# Nestling_2_1_EXB_OLED.net
KiCad netlist of a schematic drawn in Altium Designer
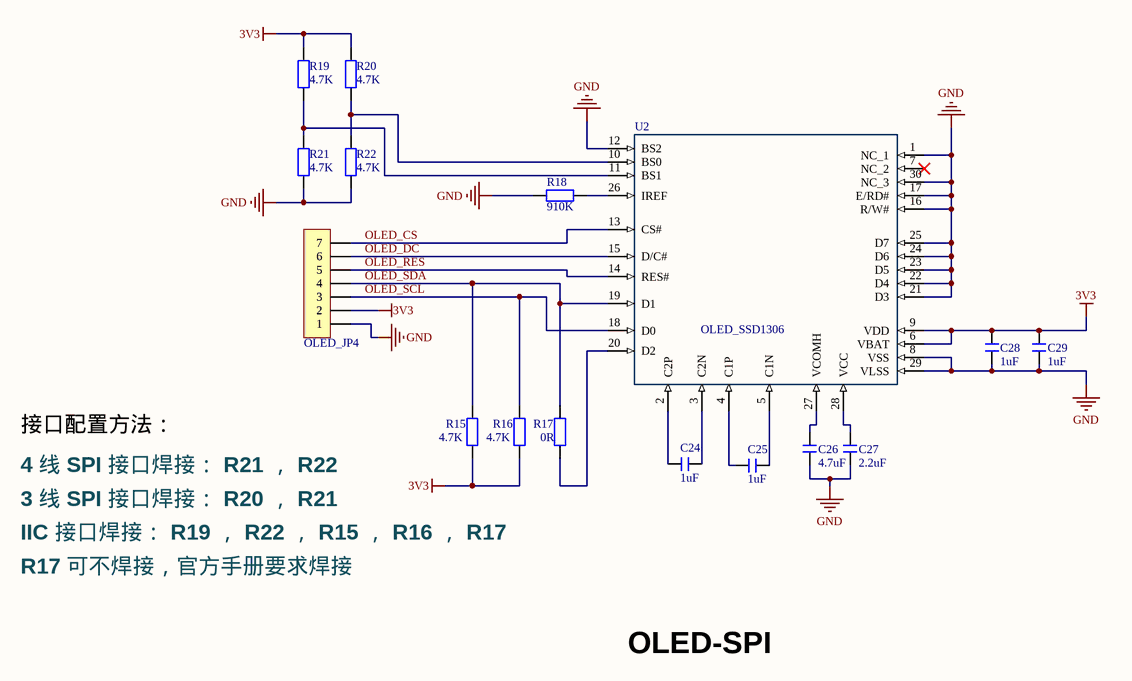
[diagram p0: Nestling_2.1_EXB_OLED.SchDoc]

(export (version "E")
  (design (tool "Eeschema 10.0.6"))
  (components
    (comp (ref "C24")
      (value "1uF")
      (footprint "C 0603_M")
      (description "无极性贴片电容")
      (fields (field (name "版权归属") "源创客"))
      (libsource (lib "altium-import") (part "root_0_C_"))
    )
    (comp (ref "C25")
      (value "1uF")
      (footprint "C 0603_M")
      (description "无极性贴片电容")
      (fields (field (name "版权归属") "源创客"))
      (libsource (lib "altium-import") (part "root_0_C_"))
    )
    (comp (ref "C26")
      (value "4.7uF")
      (footprint "C 0603_M")
      (description "无极性贴片电容")
      (fields (field (name "版权归属") "源创客"))
      (libsource (lib "altium-import") (part "root_3_C_"))
    )
    (comp (ref "C27")
      (value "2.2uF")
      (footprint "C 0603_M")
      (description "无极性贴片电容")
      (fields (field (name "版权归属") "源创客"))
      (libsource (lib "altium-import") (part "root_3_C_"))
    )
    (comp (ref "C28")
      (value "1uF")
      (footprint "C 0603_M")
      (description "无极性贴片电容")
      (fields (field (name "版权归属") "源创客"))
      (libsource (lib "altium-import") (part "root_3_C_"))
    )
    (comp (ref "C29")
      (value "1uF")
      (footprint "C 0603_M")
      (description "无极性贴片电容")
      (fields (field (name "版权归属") "源创客"))
      (libsource (lib "altium-import") (part "root_3_C_"))
    )
    (comp (ref "OLED_JP4")
      (value "HDR-1X7")
      (footprint "HDR2.54-M-LI-7P")
      (description "7P接插件")
      (fields (field (name "版权归属") "源创客"))
      (libsource (lib "altium-import") (part "root_2_Header 7_"))
    )
    (comp (ref "R15")
      (value "4.7K")
      (footprint "R 0603_M")
      (description "Resistor")
      (libsource (lib "General") (part "RES"))
    )
    (comp (ref "R16")
      (value "4.7K")
      (footprint "R 0603_M")
      (description "Resistor")
      (libsource (lib "General") (part "RES"))
    )
    (comp (ref "R17")
      (value "0R")
      (footprint "R 0603_M")
      (description "Resistor")
      (libsource (lib "General") (part "RES"))
    )
    (comp (ref "R18")
      (value "910K")
      (footprint "R 0603_M")
      (description "Resistor")
      (libsource (lib "") (part "RES_2"))
    )
    (comp (ref "R19")
      (value "4.7K")
      (footprint "R 0603_M")
      (description "Resistor")
      (libsource (lib "") (part "RES_1"))
    )
    (comp (ref "R20")
      (value "4.7K")
      (footprint "R 0603_M")
      (description "Resistor")
      (libsource (lib "") (part "RES_1"))
    )
    (comp (ref "R21")
      (value "4.7K")
      (footprint "R 0603_M")
      (description "Resistor")
      (libsource (lib "") (part "RES_1"))
    )
    (comp (ref "R22")
      (value "4.7K")
      (footprint "R 0603_M")
      (description "Resistor")
      (libsource (lib "") (part "RES_1"))
    )
    (comp (ref "U2")
      (value "OLED_SSD1306")
      (footprint "30P_0.7mm")
      (description "OLED_0.96寸_SSD1306，裸屏接口")
      (libsource (lib "altium-import") (part "root_0_OLED_0.96_SSD1306_"))
    )
  )
  (nets
    (net (code "1") (name "/OLED_CS") (class "Default")
      (node (ref "OLED_JP4") (pin "7") (pinfunction "7_7") (pintype "passive"))
      (node (ref "U2") (pin "13") (pinfunction "CS#_13") (pintype "input"))
    )
    (net (code "2") (name "/OLED_DC") (class "Default")
      (node (ref "OLED_JP4") (pin "6") (pinfunction "6_6") (pintype "passive"))
      (node (ref "U2") (pin "15") (pinfunction "D/C#_15") (pintype "input"))
    )
    (net (code "3") (name "/OLED_RES") (class "Default")
      (node (ref "OLED_JP4") (pin "5") (pinfunction "5_5") (pintype "passive"))
      (node (ref "U2") (pin "14") (pinfunction "RES#_14") (pintype "input"))
    )
    (net (code "4") (name "/OLED_SCL") (class "Default")
      (node (ref "OLED_JP4") (pin "3") (pinfunction "3_3") (pintype "passive"))
      (node (ref "R16") (pin "1") (pinfunction "1_1") (pintype "passive"))
      (node (ref "U2") (pin "18") (pinfunction "D0_18") (pintype "input"))
    )
    (net (code "5") (name "/OLED_SDA") (class "Default")
      (node (ref "OLED_JP4") (pin "4") (pinfunction "4_4") (pintype "passive"))
      (node (ref "R15") (pin "1") (pinfunction "1_1") (pintype "passive"))
      (node (ref "R17") (pin "1") (pinfunction "1_1") (pintype "passive"))
      (node (ref "U2") (pin "19") (pinfunction "D1_19") (pintype "input"))
    )
    (net (code "6") (name "3V3") (class "Default")
      (node (ref "C28") (pin "1") (pinfunction "1_1") (pintype "passive"))
      (node (ref "C29") (pin "1") (pinfunction "1_1") (pintype "passive"))
      (node (ref "OLED_JP4") (pin "2") (pinfunction "2_2") (pintype "passive"))
      (node (ref "R15") (pin "2") (pinfunction "2_2") (pintype "passive"))
      (node (ref "R16") (pin "2") (pinfunction "2_2") (pintype "passive"))
      (node (ref "R19") (pin "2") (pinfunction "2_2") (pintype "passive"))
      (node (ref "R20") (pin "2") (pinfunction "2_2") (pintype "passive"))
      (node (ref "U2") (pin "6") (pinfunction "VBAT_6") (pintype "input"))
      (node (ref "U2") (pin "9") (pinfunction "VDD_9") (pintype "input"))
    )
    (net (code "7") (name "GND") (class "Default")
      (node (ref "C26") (pin "2") (pinfunction "2_2") (pintype "passive"))
      (node (ref "C27") (pin "2") (pinfunction "2_2") (pintype "passive"))
      (node (ref "C28") (pin "2") (pinfunction "2_2") (pintype "passive"))
      (node (ref "C29") (pin "2") (pinfunction "2_2") (pintype "passive"))
      (node (ref "OLED_JP4") (pin "1") (pinfunction "1_1") (pintype "passive"))
      (node (ref "R18") (pin "1") (pinfunction "1_1") (pintype "passive"))
      (node (ref "R21") (pin "1") (pinfunction "1_1") (pintype "passive"))
      (node (ref "R22") (pin "1") (pinfunction "1_1") (pintype "passive"))
      (node (ref "U2") (pin "1") (pinfunction "NC_1_1") (pintype "input"))
      (node (ref "U2") (pin "12") (pinfunction "BS2_12") (pintype "input"))
      (node (ref "U2") (pin "16") (pinfunction "R/W#_16") (pintype "input"))
      (node (ref "U2") (pin "17") (pinfunction "E/RD#_17") (pintype "input"))
      (node (ref "U2") (pin "21") (pinfunction "D3_21") (pintype "input"))
      (node (ref "U2") (pin "22") (pinfunction "D4_22") (pintype "input"))
      (node (ref "U2") (pin "23") (pinfunction "D5_23") (pintype "input"))
      (node (ref "U2") (pin "24") (pinfunction "D6_24") (pintype "input"))
      (node (ref "U2") (pin "25") (pinfunction "D7_25") (pintype "input"))
      (node (ref "U2") (pin "29") (pinfunction "VLSS_29") (pintype "input"))
      (node (ref "U2") (pin "30") (pinfunction "NC_3_30") (pintype "input"))
      (node (ref "U2") (pin "8") (pinfunction "VSS_8") (pintype "input"))
    )
    (net (code "8") (name "Net-(U2-BS0)") (class "Default")
      (node (ref "R20") (pin "1") (pinfunction "1_1") (pintype "passive"))
      (node (ref "R22") (pin "2") (pinfunction "2_2") (pintype "passive"))
      (node (ref "U2") (pin "10") (pinfunction "BS0_10") (pintype "input"))
    )
    (net (code "9") (name "Net-(U2-BS1)") (class "Default")
      (node (ref "R19") (pin "1") (pinfunction "1_1") (pintype "passive"))
      (node (ref "R21") (pin "2") (pinfunction "2_2") (pintype "passive"))
      (node (ref "U2") (pin "11") (pinfunction "BS1_11") (pintype "input"))
    )
    (net (code "10") (name "Net-(U2-C1N)") (class "Default")
      (node (ref "C25") (pin "2") (pinfunction "2_2") (pintype "passive"))
      (node (ref "U2") (pin "5") (pinfunction "C1N_5") (pintype "input"))
    )
    (net (code "11") (name "Net-(U2-C1P)") (class "Default")
      (node (ref "C25") (pin "1") (pinfunction "1_1") (pintype "passive"))
      (node (ref "U2") (pin "4") (pinfunction "C1P_4") (pintype "input"))
    )
    (net (code "12") (name "Net-(U2-C2N)") (class "Default")
      (node (ref "C24") (pin "2") (pinfunction "2_2") (pintype "passive"))
      (node (ref "U2") (pin "3") (pinfunction "C2N_3") (pintype "input"))
    )
    (net (code "13") (name "Net-(U2-C2P)") (class "Default")
      (node (ref "C24") (pin "1") (pinfunction "1_1") (pintype "passive"))
      (node (ref "U2") (pin "2") (pinfunction "C2P_2") (pintype "input"))
    )
    (net (code "14") (name "Net-(U2-D2)") (class "Default")
      (node (ref "R17") (pin "2") (pinfunction "2_2") (pintype "passive"))
      (node (ref "U2") (pin "20") (pinfunction "D2_20") (pintype "input"))
    )
    (net (code "15") (name "Net-(U2-IREF)") (class "Default")
      (node (ref "R18") (pin "2") (pinfunction "2_2") (pintype "passive"))
      (node (ref "U2") (pin "26") (pinfunction "IREF_26") (pintype "input"))
    )
    (net (code "16") (name "Net-(U2-VCC)") (class "Default")
      (node (ref "C27") (pin "1") (pinfunction "1_1") (pintype "passive"))
      (node (ref "U2") (pin "28") (pinfunction "VCC_28") (pintype "input"))
    )
    (net (code "17") (name "Net-(U2-VCOMH)") (class "Default")
      (node (ref "C26") (pin "1") (pinfunction "1_1") (pintype "passive"))
      (node (ref "U2") (pin "27") (pinfunction "VCOMH_27") (pintype "input"))
    )
    (net (code "18") (name "unconnected-(U2-NC_2-Pad7)") (class "Default")
      (node (ref "U2") (pin "7") (pinfunction "NC_2_7") (pintype "input+no_connect"))
    )
  )
)
